# RocketWatch-BOTTOM.net
KiCad netlist of a schematic drawn in EAGLE
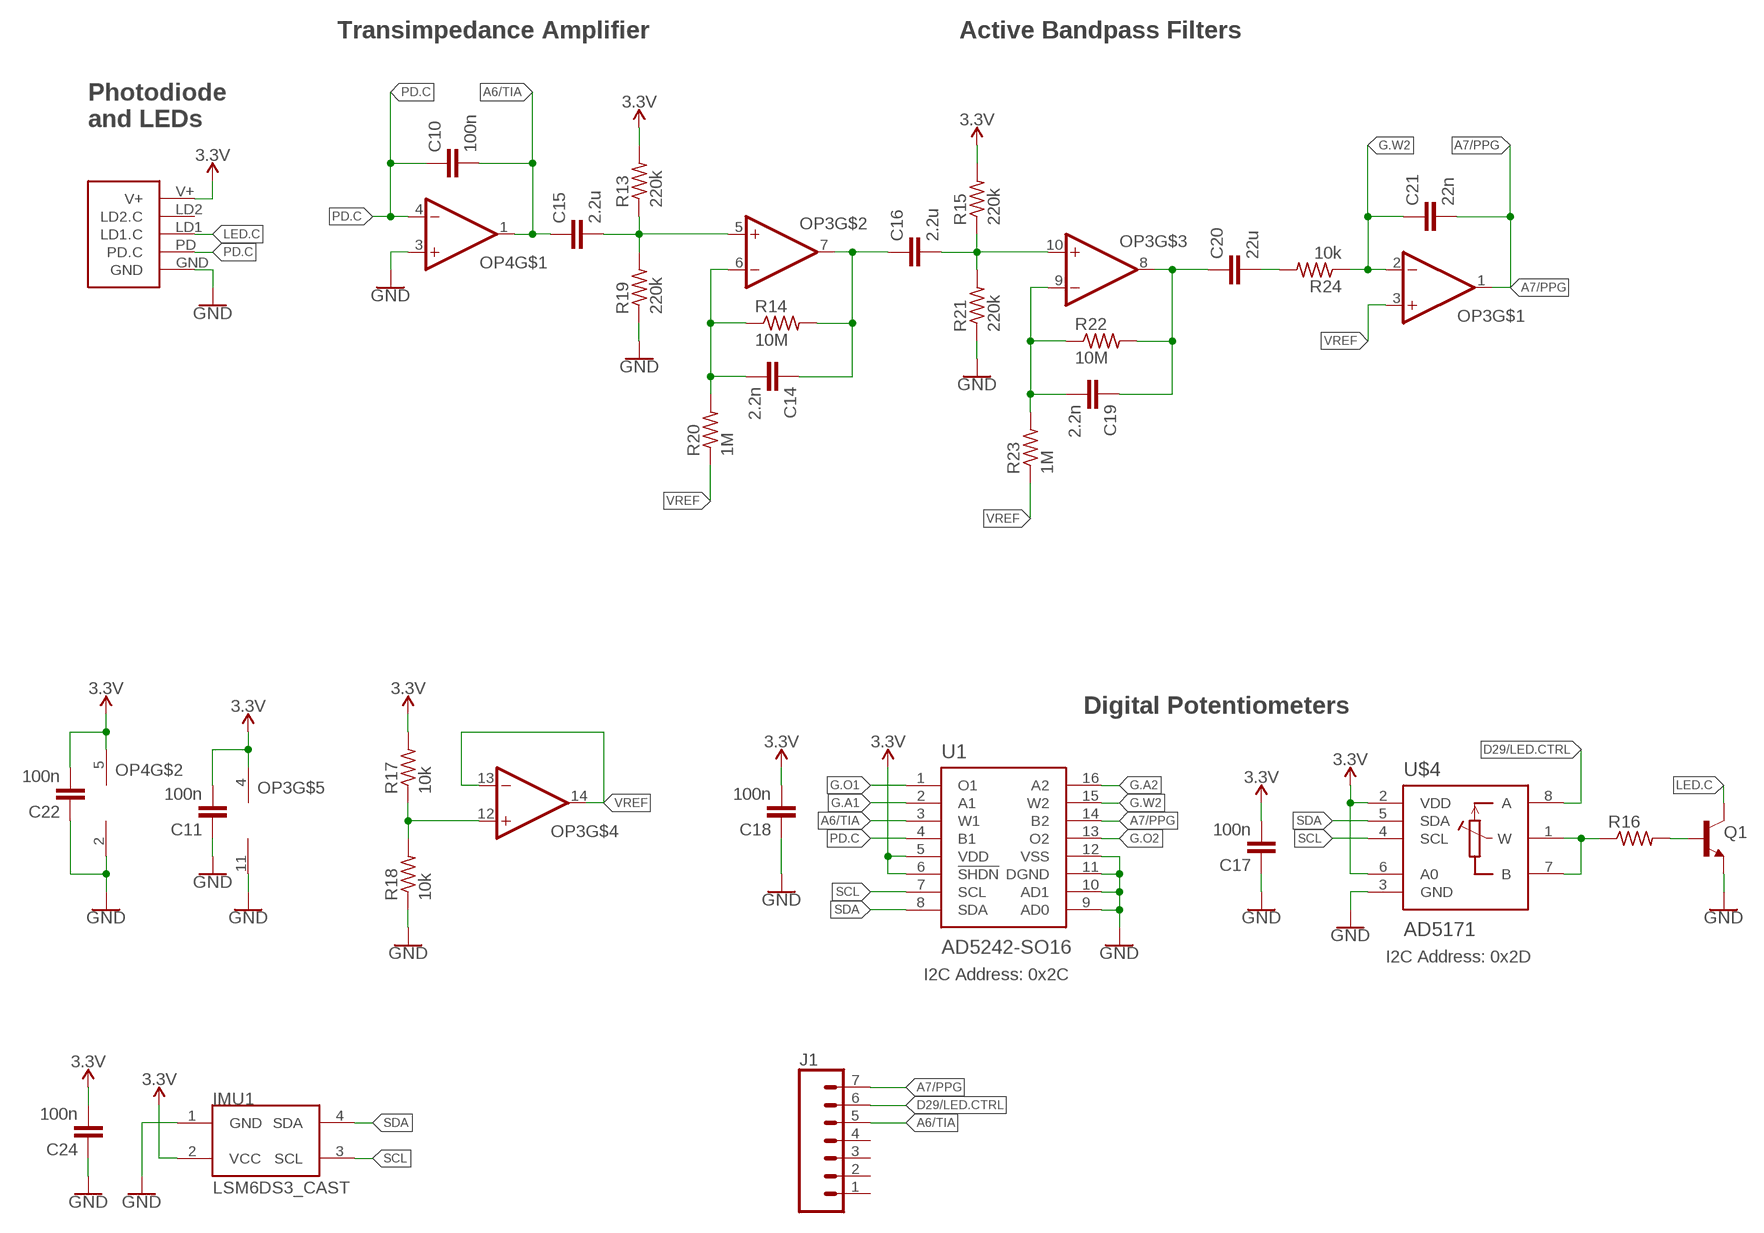
[diagram p0: schematic, sheet 1]

(export (version "E")
  (design (tool "Eeschema 10.0.6"))
  (components
    (comp (ref "C10")
      (value "100n")
      (footprint "eagle-import:C0603")
      (libsource (lib "eagle-import") (part "CAPACITOR0603"))
    )
    (comp (ref "C11")
      (value "100n")
      (footprint "eagle-import:C0603")
      (libsource (lib "eagle-import") (part "CAPACITOR0603"))
    )
    (comp (ref "C14")
      (value "2.2n")
      (footprint "eagle-import:C0603")
      (libsource (lib "eagle-import") (part "CAPACITOR0603"))
    )
    (comp (ref "C15")
      (value "2.2u")
      (footprint "eagle-import:C0603")
      (libsource (lib "eagle-import") (part "CAPACITOR0603"))
    )
    (comp (ref "C16")
      (value "2.2u")
      (footprint "eagle-import:C0603")
      (libsource (lib "eagle-import") (part "CAPACITOR0603"))
    )
    (comp (ref "C17")
      (value "100n")
      (footprint "eagle-import:C0603")
      (libsource (lib "eagle-import") (part "CAPACITOR0603"))
    )
    (comp (ref "C18")
      (value "100n")
      (footprint "eagle-import:C0603")
      (libsource (lib "eagle-import") (part "CAPACITOR0603"))
    )
    (comp (ref "C19")
      (value "2.2n")
      (footprint "eagle-import:C0603")
      (libsource (lib "eagle-import") (part "CAPACITOR0603"))
    )
    (comp (ref "C20")
      (value "22u")
      (footprint "eagle-import:C0603")
      (libsource (lib "eagle-import") (part "CAPACITOR0603"))
    )
    (comp (ref "C21")
      (value "22n")
      (footprint "eagle-import:C0603")
      (libsource (lib "eagle-import") (part "CAPACITOR0603"))
    )
    (comp (ref "C22")
      (value "100n")
      (footprint "eagle-import:C0603")
      (libsource (lib "eagle-import") (part "CAPACITOR0603"))
    )
    (comp (ref "C24")
      (value "100n")
      (footprint "eagle-import:C0603")
      (libsource (lib "eagle-import") (part "CAPACITOR0603"))
    )
    (comp (ref "IMU1")
      (value "LSM6DS3_CAST")
      (footprint "eagle-import:LSM6DS3_CAST")
      (libsource (lib "eagle-import") (part "LSM6DS3_CAST"))
    )
    (comp (ref "J1")
      (value "CONN_07")
      (footprint "eagle-import:1X07")
      (libsource (lib "eagle-import") (part "CONN_07"))
    )
    (comp (ref "OP3")
      (value "OP-QUAD-SO14")
      (footprint "eagle-import:SO14")
      (libsource (lib "eagle-import") (part "OP-QUAD-SO14"))
    )
    (comp (ref "OP4")
      (value "OP-SINGLEOT")
      (footprint "eagle-import:SOT23-5")
      (libsource (lib "eagle-import") (part "OP-SINGLEOT"))
    )
    (comp (ref "Q1")
      (value "NPN-GENERIC")
      (footprint "eagle-import:SOT23-3")
      (libsource (lib "eagle-import") (part "NPN-GENERIC"))
    )
    (comp (ref "R13")
      (value "220k")
      (footprint "eagle-import:R0603")
      (libsource (lib "eagle-import") (part "RESISTOR0603"))
    )
    (comp (ref "R14")
      (value "10M")
      (footprint "eagle-import:R0603")
      (libsource (lib "eagle-import") (part "RESISTOR0603"))
    )
    (comp (ref "R15")
      (value "220k")
      (footprint "eagle-import:R0603")
      (libsource (lib "eagle-import") (part "RESISTOR0603"))
    )
    (comp (ref "R16")
      (value "RESISTOR0603")
      (footprint "eagle-import:R0603")
      (libsource (lib "eagle-import") (part "RESISTOR0603"))
    )
    (comp (ref "R17")
      (value "10k")
      (footprint "eagle-import:R0402")
      (libsource (lib "eagle-import") (part "RESISTOR0402"))
    )
    (comp (ref "R18")
      (value "10k")
      (footprint "eagle-import:R0402")
      (libsource (lib "eagle-import") (part "RESISTOR0402"))
    )
    (comp (ref "R19")
      (value "220k")
      (footprint "eagle-import:R0603")
      (libsource (lib "eagle-import") (part "RESISTOR0603"))
    )
    (comp (ref "R20")
      (value "1M")
      (footprint "eagle-import:R0603")
      (libsource (lib "eagle-import") (part "RESISTOR0603"))
    )
    (comp (ref "R21")
      (value "220k")
      (footprint "eagle-import:R0603")
      (libsource (lib "eagle-import") (part "RESISTOR0603"))
    )
    (comp (ref "R22")
      (value "10M")
      (footprint "eagle-import:R0603")
      (libsource (lib "eagle-import") (part "RESISTOR0603"))
    )
    (comp (ref "R23")
      (value "1M")
      (footprint "eagle-import:R0603")
      (libsource (lib "eagle-import") (part "RESISTOR0603"))
    )
    (comp (ref "R24")
      (value "10k")
      (footprint "eagle-import:R0603")
      (libsource (lib "eagle-import") (part "RESISTOR0603"))
    )
    (comp (ref "U$3")
      (value "PPG.MODULE.2")
      (footprint "eagle-import:PPG.MODULE.2")
      (libsource (lib "eagle-import") (part "PPG.MODULE.2"))
    )
    (comp (ref "U$4")
      (value "AD5171")
      (footprint "eagle-import:SOT-23-8")
      (libsource (lib "eagle-import") (part "AD5171"))
    )
    (comp (ref "U1")
      (value "AD5242-SO16")
      (footprint "eagle-import:SO16")
      (libsource (lib "eagle-import") (part "AD5242-SO16"))
    )
  )
  (nets
    (net (code "1") (name "3.3V") (class "Default")
      (node (ref "C11") (pin "2") (pinfunction "2_2") (pintype "passive"))
      (node (ref "C17") (pin "2") (pinfunction "2_2") (pintype "passive"))
      (node (ref "C18") (pin "2") (pinfunction "2_2") (pintype "passive"))
      (node (ref "C22") (pin "2") (pinfunction "2_2") (pintype "passive"))
      (node (ref "C24") (pin "2") (pinfunction "2_2") (pintype "passive"))
      (node (ref "IMU1") (pin "2") (pinfunction "VCC_2") (pintype "bidirectional"))
      (node (ref "OP3") (pin "4") (pinfunction "V+_4") (pintype "power_in"))
      (node (ref "OP4") (pin "5") (pinfunction "V+_5") (pintype "power_in"))
      (node (ref "R13") (pin "2") (pinfunction "2_2") (pintype "passive"))
      (node (ref "R15") (pin "2") (pinfunction "2_2") (pintype "passive"))
      (node (ref "R17") (pin "2") (pinfunction "2_2") (pintype "passive"))
      (node (ref "U$3") (pin "V+") (pinfunction "V+_V+") (pintype "bidirectional"))
      (node (ref "U$4") (pin "2") (pinfunction "VDD_2") (pintype "bidirectional"))
      (node (ref "U$4") (pin "6") (pinfunction "A0_6") (pintype "bidirectional"))
      (node (ref "U1") (pin "5") (pinfunction "VDD_5") (pintype "bidirectional"))
      (node (ref "U1") (pin "6") (pinfunction "~{SHDN}_6") (pintype "bidirectional"))
    )
    (net (code "2") (name "A6{slash}TIA") (class "Default")
      (node (ref "C10") (pin "2") (pinfunction "2_2") (pintype "passive"))
      (node (ref "C15") (pin "1") (pinfunction "1_1") (pintype "passive"))
      (node (ref "J1") (pin "5") (pinfunction "5_5") (pintype "passive"))
      (node (ref "OP4") (pin "1") (pinfunction "OUT_1") (pintype "output"))
      (node (ref "U1") (pin "3") (pinfunction "W1_3") (pintype "bidirectional"))
    )
    (net (code "3") (name "A7{slash}PPG") (class "Default")
      (node (ref "C21") (pin "2") (pinfunction "2_2") (pintype "passive"))
      (node (ref "J1") (pin "7") (pinfunction "7_7") (pintype "passive"))
      (node (ref "OP3") (pin "1") (pinfunction "OUT_1") (pintype "output"))
      (node (ref "U1") (pin "14") (pinfunction "B2_14") (pintype "bidirectional"))
    )
    (net (code "4") (name "D29{slash}LED.CTRL") (class "Default")
      (node (ref "J1") (pin "6") (pinfunction "6_6") (pintype "passive"))
      (node (ref "U$4") (pin "8") (pinfunction "A_8") (pintype "bidirectional"))
    )
    (net (code "5") (name "G.A1") (class "Default")
      (node (ref "U1") (pin "2") (pinfunction "A1_2") (pintype "bidirectional"))
    )
    (net (code "6") (name "G.A2") (class "Default")
      (node (ref "U1") (pin "16") (pinfunction "A2_16") (pintype "bidirectional"))
    )
    (net (code "7") (name "G.O1") (class "Default")
      (node (ref "U1") (pin "1") (pinfunction "O1_1") (pintype "bidirectional"))
    )
    (net (code "8") (name "G.O2") (class "Default")
      (node (ref "U1") (pin "13") (pinfunction "O2_13") (pintype "bidirectional"))
    )
    (net (code "9") (name "G.W2") (class "Default")
      (node (ref "C21") (pin "1") (pinfunction "1_1") (pintype "passive"))
      (node (ref "OP3") (pin "2") (pinfunction "-IN_2") (pintype "input"))
      (node (ref "R24") (pin "1") (pinfunction "1_1") (pintype "passive"))
      (node (ref "U1") (pin "15") (pinfunction "W2_15") (pintype "bidirectional"))
    )
    (net (code "10") (name "GND") (class "Default")
      (node (ref "C11") (pin "1") (pinfunction "1_1") (pintype "passive"))
      (node (ref "C17") (pin "1") (pinfunction "1_1") (pintype "passive"))
      (node (ref "C18") (pin "1") (pinfunction "1_1") (pintype "passive"))
      (node (ref "C22") (pin "1") (pinfunction "1_1") (pintype "passive"))
      (node (ref "C24") (pin "1") (pinfunction "1_1") (pintype "passive"))
      (node (ref "IMU1") (pin "1") (pinfunction "GND_1") (pintype "bidirectional"))
      (node (ref "OP3") (pin "11") (pinfunction "V-_11") (pintype "power_in"))
      (node (ref "OP4") (pin "2") (pinfunction "V-_2") (pintype "power_in"))
      (node (ref "OP4") (pin "3") (pinfunction "+IN_3") (pintype "input"))
      (node (ref "Q1") (pin "2") (pinfunction "E_2") (pintype "passive"))
      (node (ref "R18") (pin "1") (pinfunction "1_1") (pintype "passive"))
      (node (ref "R19") (pin "1") (pinfunction "1_1") (pintype "passive"))
      (node (ref "R21") (pin "1") (pinfunction "1_1") (pintype "passive"))
      (node (ref "U$3") (pin "GND") (pinfunction "GND_GND") (pintype "bidirectional"))
      (node (ref "U$4") (pin "3") (pinfunction "GND_3") (pintype "bidirectional"))
      (node (ref "U1") (pin "10") (pinfunction "AD1_10") (pintype "bidirectional"))
      (node (ref "U1") (pin "11") (pinfunction "DGND_11") (pintype "bidirectional"))
      (node (ref "U1") (pin "12") (pinfunction "VSS_12") (pintype "bidirectional"))
      (node (ref "U1") (pin "9") (pinfunction "AD0_9") (pintype "bidirectional"))
    )
    (net (code "11") (name "LED.C") (class "Default")
      (node (ref "Q1") (pin "3") (pinfunction "C_3") (pintype "passive"))
      (node (ref "U$3") (pin "LD1") (pinfunction "LD1.C_LD1") (pintype "bidirectional"))
    )
    (net (code "12") (name "Net-(C20-Pad2)") (class "Default")
      (node (ref "C20") (pin "2") (pinfunction "2_2") (pintype "passive"))
      (node (ref "R24") (pin "2") (pinfunction "2_2") (pintype "passive"))
    )
    (net (code "13") (name "Net-(OP3B-+IN)") (class "Default")
      (node (ref "C15") (pin "2") (pinfunction "2_2") (pintype "passive"))
      (node (ref "OP3") (pin "5") (pinfunction "+IN_5") (pintype "input"))
      (node (ref "R13") (pin "1") (pinfunction "1_1") (pintype "passive"))
      (node (ref "R19") (pin "2") (pinfunction "2_2") (pintype "passive"))
    )
    (net (code "14") (name "Net-(OP3B--IN)") (class "Default")
      (node (ref "C14") (pin "2") (pinfunction "2_2") (pintype "passive"))
      (node (ref "OP3") (pin "6") (pinfunction "-IN_6") (pintype "input"))
      (node (ref "R14") (pin "1") (pinfunction "1_1") (pintype "passive"))
      (node (ref "R20") (pin "2") (pinfunction "2_2") (pintype "passive"))
    )
    (net (code "15") (name "Net-(OP3B-OUT)") (class "Default")
      (node (ref "C14") (pin "1") (pinfunction "1_1") (pintype "passive"))
      (node (ref "C16") (pin "1") (pinfunction "1_1") (pintype "passive"))
      (node (ref "OP3") (pin "7") (pinfunction "OUT_7") (pintype "output"))
      (node (ref "R14") (pin "2") (pinfunction "2_2") (pintype "passive"))
    )
    (net (code "16") (name "Net-(OP3C-+IN)") (class "Default")
      (node (ref "C16") (pin "2") (pinfunction "2_2") (pintype "passive"))
      (node (ref "OP3") (pin "10") (pinfunction "+IN_10") (pintype "input"))
      (node (ref "R15") (pin "1") (pinfunction "1_1") (pintype "passive"))
      (node (ref "R21") (pin "2") (pinfunction "2_2") (pintype "passive"))
    )
    (net (code "17") (name "Net-(OP3C--IN)") (class "Default")
      (node (ref "C19") (pin "2") (pinfunction "2_2") (pintype "passive"))
      (node (ref "OP3") (pin "9") (pinfunction "-IN_9") (pintype "input"))
      (node (ref "R22") (pin "1") (pinfunction "1_1") (pintype "passive"))
      (node (ref "R23") (pin "2") (pinfunction "2_2") (pintype "passive"))
    )
    (net (code "18") (name "Net-(OP3C-OUT)") (class "Default")
      (node (ref "C19") (pin "1") (pinfunction "1_1") (pintype "passive"))
      (node (ref "C20") (pin "1") (pinfunction "1_1") (pintype "passive"))
      (node (ref "OP3") (pin "8") (pinfunction "OUT_8") (pintype "output"))
      (node (ref "R22") (pin "2") (pinfunction "2_2") (pintype "passive"))
    )
    (net (code "19") (name "Net-(OP3D-+IN)") (class "Default")
      (node (ref "OP3") (pin "12") (pinfunction "+IN_12") (pintype "input"))
      (node (ref "R17") (pin "1") (pinfunction "1_1") (pintype "passive"))
      (node (ref "R18") (pin "2") (pinfunction "2_2") (pintype "passive"))
    )
    (net (code "20") (name "Net-(Q1-B)") (class "Default")
      (node (ref "Q1") (pin "1") (pinfunction "B_1") (pintype "passive"))
      (node (ref "R16") (pin "2") (pinfunction "2_2") (pintype "passive"))
    )
    (net (code "21") (name "Net-(U$4-B)") (class "Default")
      (node (ref "R16") (pin "1") (pinfunction "1_1") (pintype "passive"))
      (node (ref "U$4") (pin "1") (pinfunction "W_1") (pintype "bidirectional"))
      (node (ref "U$4") (pin "7") (pinfunction "B_7") (pintype "bidirectional"))
    )
    (net (code "22") (name "PD.C") (class "Default")
      (node (ref "C10") (pin "1") (pinfunction "1_1") (pintype "passive"))
      (node (ref "OP4") (pin "4") (pinfunction "-IN_4") (pintype "input"))
      (node (ref "U$3") (pin "PD") (pinfunction "PD.C_PD") (pintype "bidirectional"))
      (node (ref "U1") (pin "4") (pinfunction "B1_4") (pintype "bidirectional"))
    )
    (net (code "23") (name "SCL") (class "Default")
      (node (ref "IMU1") (pin "3") (pinfunction "SCL_3") (pintype "bidirectional"))
      (node (ref "U$4") (pin "4") (pinfunction "SCL_4") (pintype "bidirectional"))
      (node (ref "U1") (pin "7") (pinfunction "SCL_7") (pintype "bidirectional"))
    )
    (net (code "24") (name "SDA") (class "Default")
      (node (ref "IMU1") (pin "4") (pinfunction "SDA_4") (pintype "bidirectional"))
      (node (ref "U$4") (pin "5") (pinfunction "SDA_5") (pintype "bidirectional"))
      (node (ref "U1") (pin "8") (pinfunction "SDA_8") (pintype "bidirectional"))
    )
    (net (code "25") (name "VREF") (class "Default")
      (node (ref "OP3") (pin "13") (pinfunction "-IN_13") (pintype "input"))
      (node (ref "OP3") (pin "14") (pinfunction "OUT_14") (pintype "output"))
      (node (ref "OP3") (pin "3") (pinfunction "+IN_3") (pintype "input"))
      (node (ref "R20") (pin "1") (pinfunction "1_1") (pintype "passive"))
      (node (ref "R23") (pin "1") (pinfunction "1_1") (pintype "passive"))
    )
    (net (code "26") (name "unconnected-(J1-Pad1)") (class "Default")
      (node (ref "J1") (pin "1") (pinfunction "1_1") (pintype "passive"))
    )
    (net (code "27") (name "unconnected-(J1-Pad2)") (class "Default")
      (node (ref "J1") (pin "2") (pinfunction "2_2") (pintype "passive"))
    )
    (net (code "28") (name "unconnected-(J1-Pad3)") (class "Default")
      (node (ref "J1") (pin "3") (pinfunction "3_3") (pintype "passive"))
    )
    (net (code "29") (name "unconnected-(J1-Pad4)") (class "Default")
      (node (ref "J1") (pin "4") (pinfunction "4_4") (pintype "passive"))
    )
    (net (code "30") (name "unconnected-(U$3-LD2.C-PadLD2)") (class "Default")
      (node (ref "U$3") (pin "LD2") (pinfunction "LD2.C_LD2") (pintype "bidirectional"))
    )
  )
)
